# SunnysideTimerV1.net
KiCad netlist of a schematic drawn in EAGLE
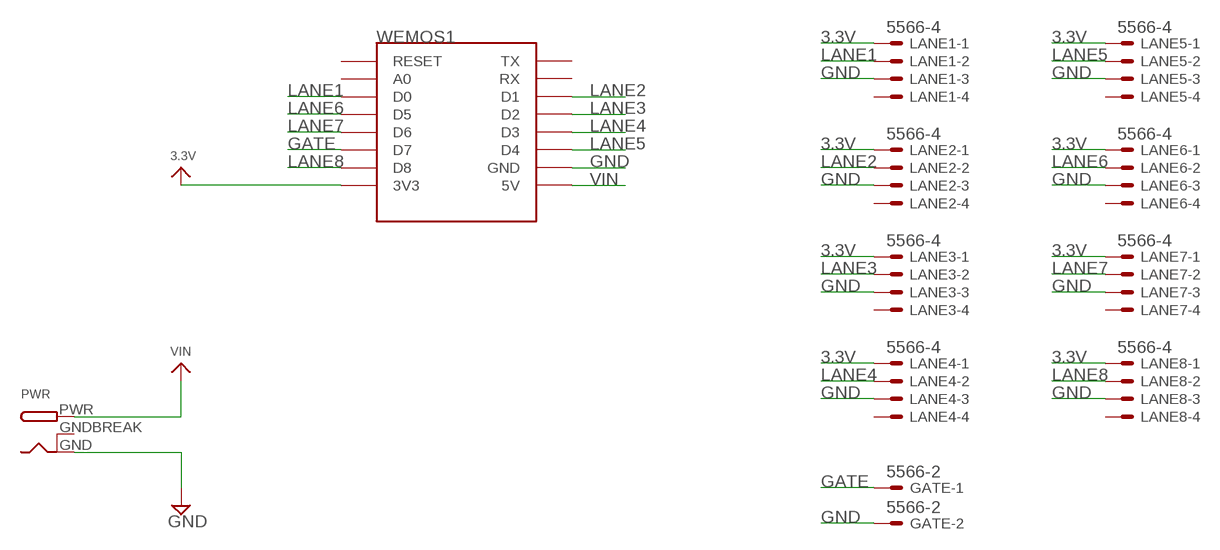
[diagram p0: schematic, sheet 1]

(export (version "E")
  (design (tool "Eeschema 10.0.6"))
  (components
    (comp (ref "GATE")
      (value "5566-2")
      (footprint "eagle-import:5566-2")
      (libsource (lib "eagle-import") (part "5566-2"))
    )
    (comp (ref "LANE1")
      (value "5566-4")
      (footprint "eagle-import:5566-4")
      (libsource (lib "eagle-import") (part "5566-4"))
    )
    (comp (ref "LANE2")
      (value "5566-4")
      (footprint "eagle-import:5566-4")
      (libsource (lib "eagle-import") (part "5566-4"))
    )
    (comp (ref "LANE3")
      (value "5566-4")
      (footprint "eagle-import:5566-4")
      (libsource (lib "eagle-import") (part "5566-4"))
    )
    (comp (ref "LANE4")
      (value "5566-4")
      (footprint "eagle-import:5566-4")
      (libsource (lib "eagle-import") (part "5566-4"))
    )
    (comp (ref "LANE5")
      (value "5566-4")
      (footprint "eagle-import:5566-4")
      (libsource (lib "eagle-import") (part "5566-4"))
    )
    (comp (ref "LANE6")
      (value "5566-4")
      (footprint "eagle-import:5566-4")
      (libsource (lib "eagle-import") (part "5566-4"))
    )
    (comp (ref "LANE7")
      (value "5566-4")
      (footprint "eagle-import:5566-4")
      (libsource (lib "eagle-import") (part "5566-4"))
    )
    (comp (ref "LANE8")
      (value "5566-4")
      (footprint "eagle-import:5566-4")
      (libsource (lib "eagle-import") (part "5566-4"))
    )
    (comp (ref "PWR")
      (value "DCBARRELPTH")
      (footprint "eagle-import:DCJACK_2MM_PTH")
      (libsource (lib "eagle-import") (part "DCBARRELPTH"))
    )
    (comp (ref "WEMOS1")
      (value "WEMOS-D1-MINI")
      (footprint "eagle-import:WEMOS-D1-MINI")
      (libsource (lib "eagle-import") (part "WEMOS-D1-MINI"))
    )
  )
  (nets
    (net (code "1") (name "/GATE") (class "Default")
      (node (ref "GATE") (pin "1") (pinfunction "S_1") (pintype "passive"))
      (node (ref "WEMOS1") (pin "D7") (pinfunction "D7_D7") (pintype "bidirectional"))
    )
    (net (code "2") (name "/GNDBREAK") (class "Default")
      (node (ref "PWR") (pin "GNDBREAK") (pinfunction "GNDBREAK_GNDBREAK") (pintype "power_in"))
    )
    (net (code "3") (name "/LANE1") (class "Default")
      (node (ref "LANE1") (pin "2") (pinfunction "S_2") (pintype "passive"))
      (node (ref "WEMOS1") (pin "D0") (pinfunction "D0_D0") (pintype "bidirectional"))
    )
    (net (code "4") (name "/LANE2") (class "Default")
      (node (ref "LANE2") (pin "2") (pinfunction "S_2") (pintype "passive"))
      (node (ref "WEMOS1") (pin "D1") (pinfunction "D1_D1") (pintype "bidirectional"))
    )
    (net (code "5") (name "/LANE3") (class "Default")
      (node (ref "LANE3") (pin "2") (pinfunction "S_2") (pintype "passive"))
      (node (ref "WEMOS1") (pin "D2") (pinfunction "D2_D2") (pintype "bidirectional"))
    )
    (net (code "6") (name "/LANE4") (class "Default")
      (node (ref "LANE4") (pin "2") (pinfunction "S_2") (pintype "passive"))
      (node (ref "WEMOS1") (pin "D3") (pinfunction "D3_D3") (pintype "bidirectional"))
    )
    (net (code "7") (name "/LANE5") (class "Default")
      (node (ref "LANE5") (pin "2") (pinfunction "S_2") (pintype "passive"))
      (node (ref "WEMOS1") (pin "D4") (pinfunction "D4_D4") (pintype "bidirectional"))
    )
    (net (code "8") (name "/LANE6") (class "Default")
      (node (ref "LANE6") (pin "2") (pinfunction "S_2") (pintype "passive"))
      (node (ref "WEMOS1") (pin "D5") (pinfunction "D5_D5") (pintype "bidirectional"))
    )
    (net (code "9") (name "/LANE7") (class "Default")
      (node (ref "LANE7") (pin "2") (pinfunction "S_2") (pintype "passive"))
      (node (ref "WEMOS1") (pin "D6") (pinfunction "D6_D6") (pintype "bidirectional"))
    )
    (net (code "10") (name "/LANE8") (class "Default")
      (node (ref "LANE8") (pin "2") (pinfunction "S_2") (pintype "passive"))
      (node (ref "WEMOS1") (pin "D8") (pinfunction "D8_D8") (pintype "bidirectional"))
    )
    (net (code "11") (name "3.3V") (class "Default")
      (node (ref "LANE1") (pin "1") (pinfunction "S_1") (pintype "passive"))
      (node (ref "LANE2") (pin "1") (pinfunction "S_1") (pintype "passive"))
      (node (ref "LANE3") (pin "1") (pinfunction "S_1") (pintype "passive"))
      (node (ref "LANE4") (pin "1") (pinfunction "S_1") (pintype "passive"))
      (node (ref "LANE5") (pin "1") (pinfunction "S_1") (pintype "passive"))
      (node (ref "LANE6") (pin "1") (pinfunction "S_1") (pintype "passive"))
      (node (ref "LANE7") (pin "1") (pinfunction "S_1") (pintype "passive"))
      (node (ref "LANE8") (pin "1") (pinfunction "S_1") (pintype "passive"))
      (node (ref "WEMOS1") (pin "3V3") (pinfunction "3V3_3V3") (pintype "bidirectional"))
    )
    (net (code "12") (name "GND") (class "Default")
      (node (ref "GATE") (pin "2") (pinfunction "S_2") (pintype "passive"))
      (node (ref "LANE1") (pin "3") (pinfunction "S_3") (pintype "passive"))
      (node (ref "LANE2") (pin "3") (pinfunction "S_3") (pintype "passive"))
      (node (ref "LANE3") (pin "3") (pinfunction "S_3") (pintype "passive"))
      (node (ref "LANE4") (pin "3") (pinfunction "S_3") (pintype "passive"))
      (node (ref "LANE5") (pin "3") (pinfunction "S_3") (pintype "passive"))
      (node (ref "LANE6") (pin "3") (pinfunction "S_3") (pintype "passive"))
      (node (ref "LANE7") (pin "3") (pinfunction "S_3") (pintype "passive"))
      (node (ref "LANE8") (pin "3") (pinfunction "S_3") (pintype "passive"))
      (node (ref "PWR") (pin "GND") (pinfunction "GND_GND") (pintype "power_in"))
      (node (ref "WEMOS1") (pin "GND") (pinfunction "GND_GND") (pintype "bidirectional"))
    )
    (net (code "13") (name "VIN") (class "Default")
      (node (ref "PWR") (pin "PWR") (pinfunction "PWR_PWR") (pintype "power_in"))
      (node (ref "WEMOS1") (pin "5V") (pinfunction "5V_5V") (pintype "bidirectional"))
    )
    (net (code "14") (name "unconnected-(LANE1D-S-Pad4)") (class "Default")
      (node (ref "LANE1") (pin "4") (pinfunction "S_4") (pintype "passive"))
    )
    (net (code "15") (name "unconnected-(LANE2D-S-Pad4)") (class "Default")
      (node (ref "LANE2") (pin "4") (pinfunction "S_4") (pintype "passive"))
    )
    (net (code "16") (name "unconnected-(LANE3D-S-Pad4)") (class "Default")
      (node (ref "LANE3") (pin "4") (pinfunction "S_4") (pintype "passive"))
    )
    (net (code "17") (name "unconnected-(LANE4D-S-Pad4)") (class "Default")
      (node (ref "LANE4") (pin "4") (pinfunction "S_4") (pintype "passive"))
    )
    (net (code "18") (name "unconnected-(LANE5D-S-Pad4)") (class "Default")
      (node (ref "LANE5") (pin "4") (pinfunction "S_4") (pintype "passive"))
    )
    (net (code "19") (name "unconnected-(LANE6D-S-Pad4)") (class "Default")
      (node (ref "LANE6") (pin "4") (pinfunction "S_4") (pintype "passive"))
    )
    (net (code "20") (name "unconnected-(LANE7D-S-Pad4)") (class "Default")
      (node (ref "LANE7") (pin "4") (pinfunction "S_4") (pintype "passive"))
    )
    (net (code "21") (name "unconnected-(LANE8D-S-Pad4)") (class "Default")
      (node (ref "LANE8") (pin "4") (pinfunction "S_4") (pintype "passive"))
    )
    (net (code "22") (name "unconnected-(WEMOS1-PadA0)") (class "Default")
      (node (ref "WEMOS1") (pin "A0") (pinfunction "A0_A0") (pintype "bidirectional"))
    )
    (net (code "23") (name "unconnected-(WEMOS1-PadRESET)") (class "Default")
      (node (ref "WEMOS1") (pin "RESET") (pinfunction "RESET_RESET") (pintype "bidirectional"))
    )
    (net (code "24") (name "unconnected-(WEMOS1-PadRX)") (class "Default")
      (node (ref "WEMOS1") (pin "RX") (pinfunction "RX_RX") (pintype "bidirectional"))
    )
    (net (code "25") (name "unconnected-(WEMOS1-PadTX)") (class "Default")
      (node (ref "WEMOS1") (pin "TX") (pinfunction "TX_TX") (pintype "bidirectional"))
    )
  )
)
